# design.net
KiCad netlist of a schematic drawn in Altium Designer
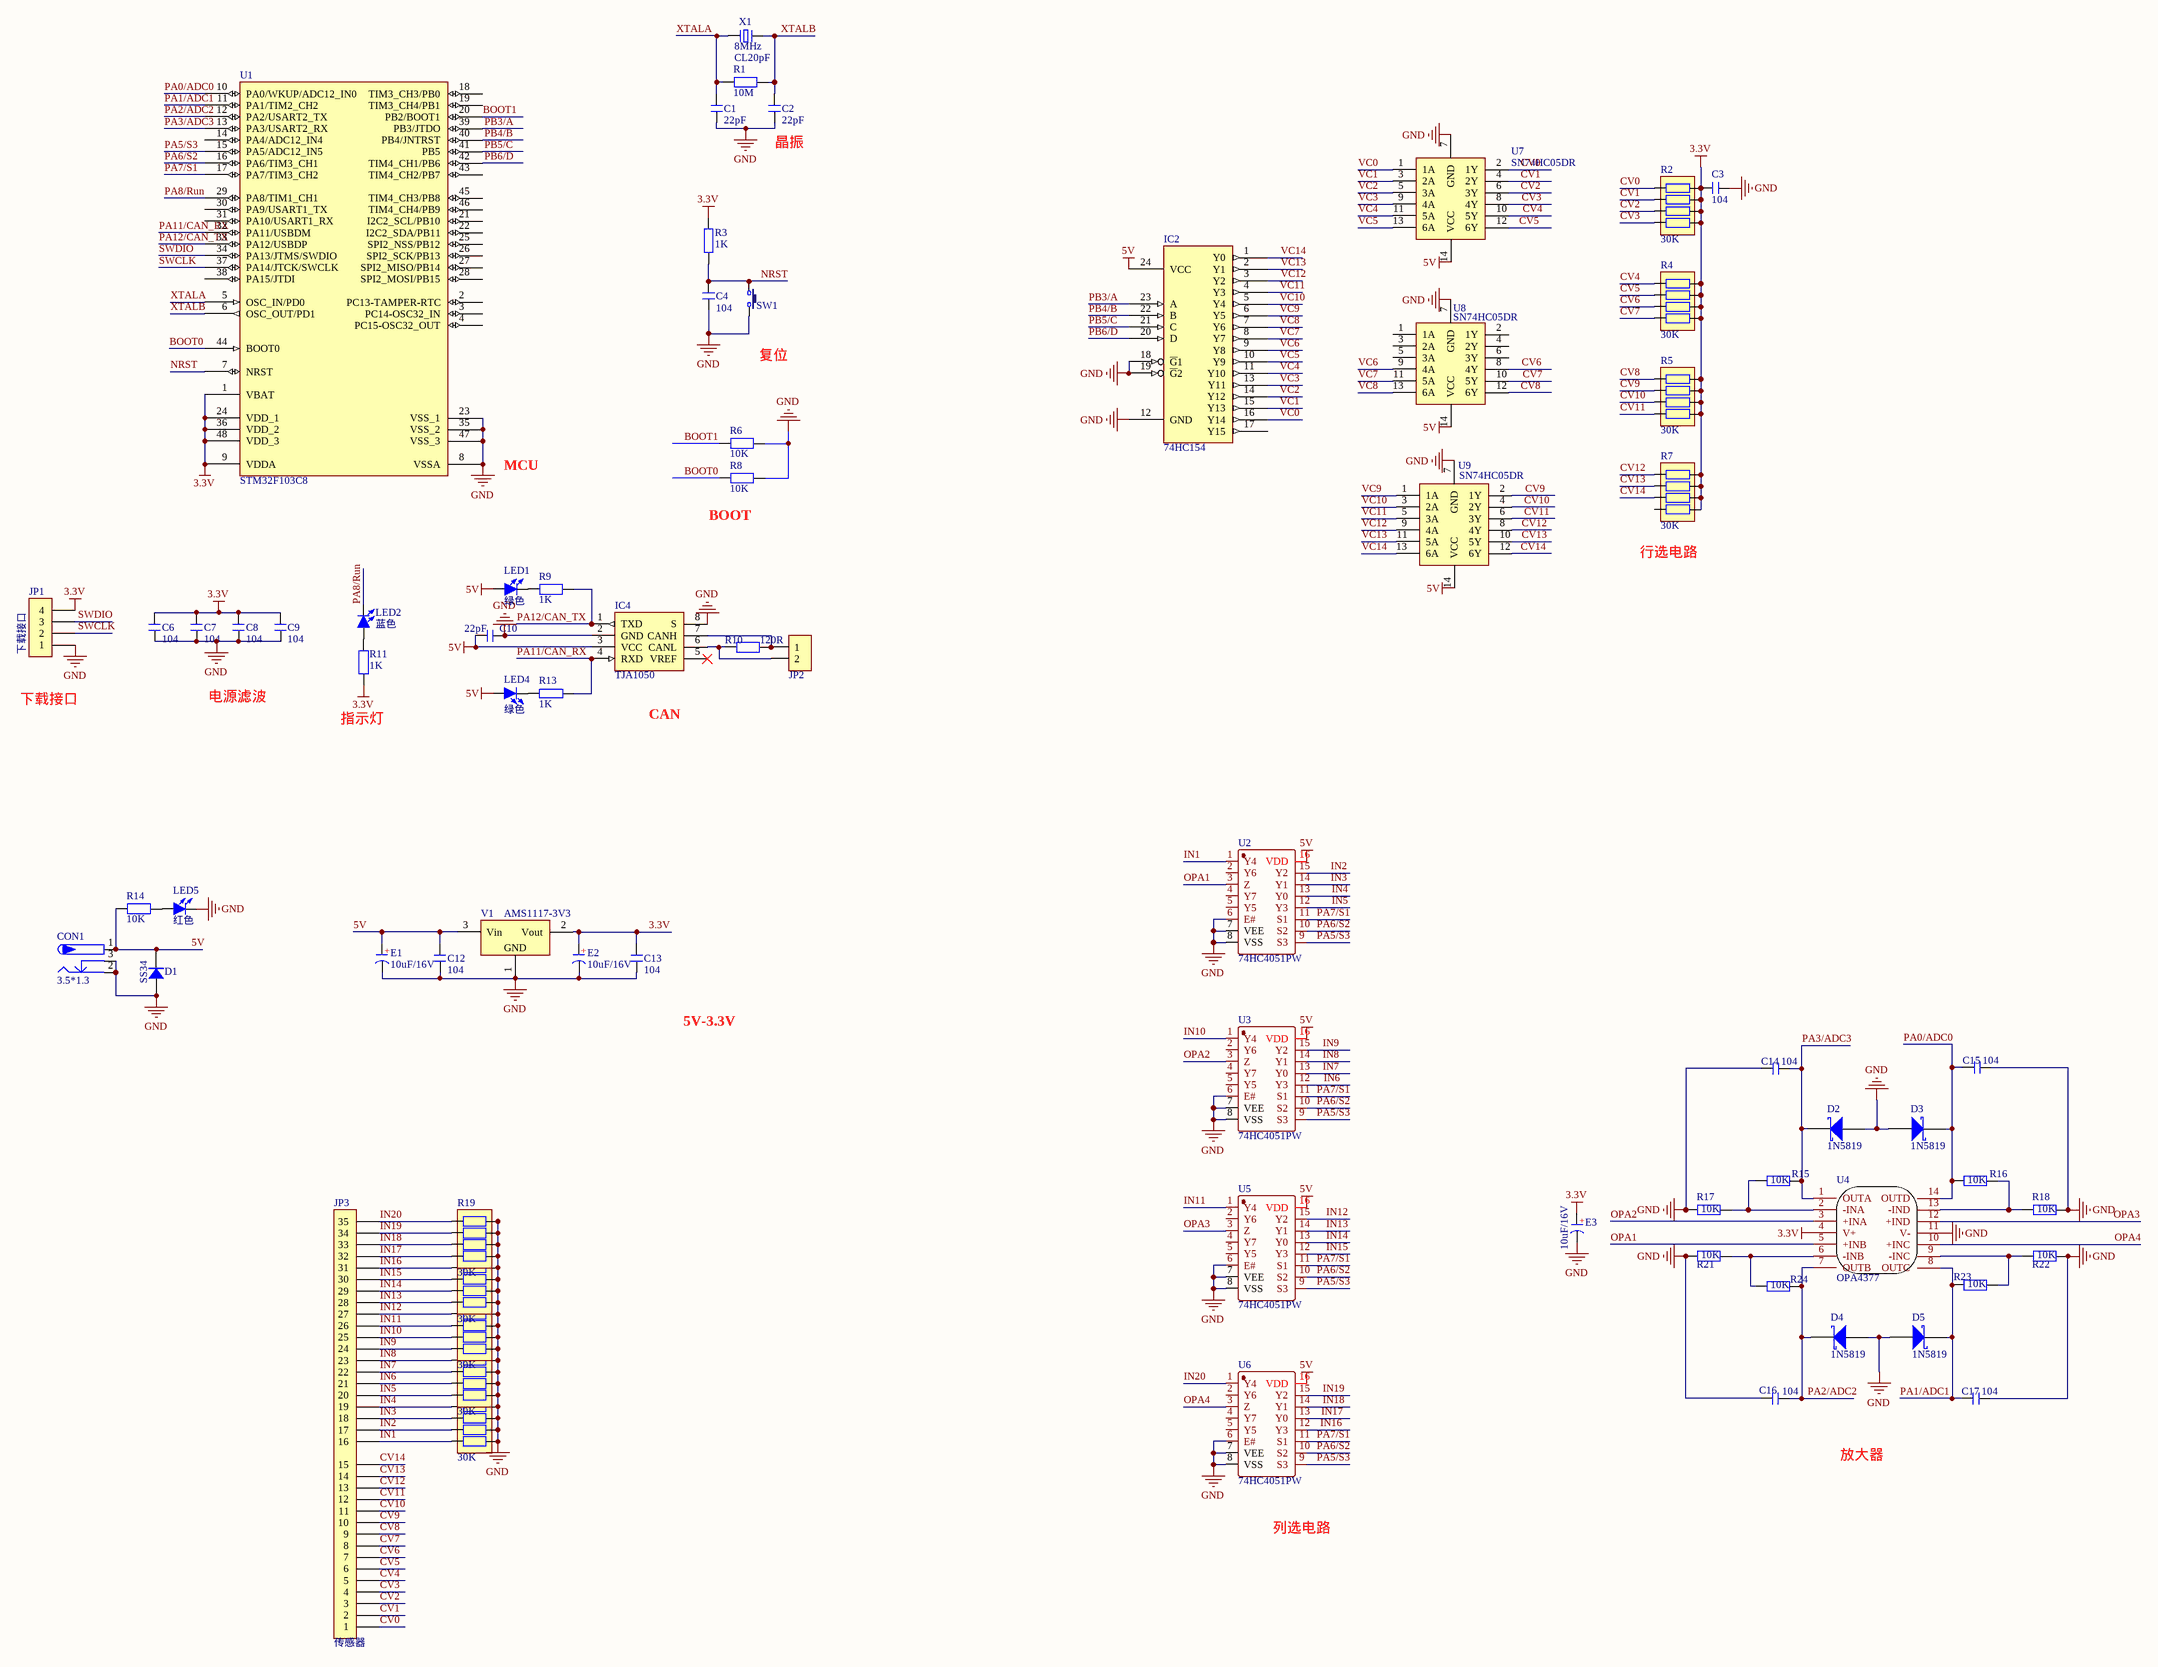
[diagram p0: 从机.SchDoc]

(export (version "E")
  (design (tool "Eeschema 10.0.6"))
  (components
    (comp (ref "C1")
      (value "22pF")
      (footprint "C 0402_L")
      (description "贴片电容")
      (libsource (lib "0.1 - 电阻-电容-电感") (part "C"))
    )
    (comp (ref "C2")
      (value "22pF")
      (footprint "C 0402_L")
      (description "贴片电容")
      (libsource (lib "0.1 - 电阻-电容-电感") (part "C"))
    )
    (comp (ref "C3")
      (value "104")
      (footprint "C 0402_L")
      (description "贴片电容")
      (libsource (lib "0.1 - 电阻-电容-电感") (part "C"))
    )
    (comp (ref "C4")
      (value "104")
      (footprint "C 0402_L")
      (description "贴片电容")
      (libsource (lib "0.1 - 电阻-电容-电感") (part "C"))
    )
    (comp (ref "C6")
      (value "104")
      (footprint "C 0402_L")
      (description "贴片电容")
      (libsource (lib "0.1 - 电阻-电容-电感") (part "C"))
    )
    (comp (ref "C7")
      (value "104")
      (footprint "C 0402_L")
      (description "贴片电容")
      (libsource (lib "0.1 - 电阻-电容-电感") (part "C"))
    )
    (comp (ref "C8")
      (value "104")
      (footprint "C 0402_L")
      (description "贴片电容")
      (libsource (lib "0.1 - 电阻-电容-电感") (part "C"))
    )
    (comp (ref "C9")
      (value "104")
      (footprint "C 0402_L")
      (description "贴片电容")
      (libsource (lib "0.1 - 电阻-电容-电感") (part "C"))
    )
    (comp (ref "C10")
      (value "22pF")
      (footprint "C 0402_L")
      (description "贴片电容")
      (libsource (lib "0.1 - 电阻-电容-电感") (part "C"))
    )
    (comp (ref "C12")
      (value "104")
      (footprint "C 0402_L")
      (description "贴片电容")
      (libsource (lib "0.1 - 电阻-电容-电感") (part "C"))
    )
    (comp (ref "C13")
      (value "104")
      (footprint "C 0402_L")
      (description "贴片电容")
      (libsource (lib "0.1 - 电阻-电容-电感") (part "C"))
    )
    (comp (ref "C14")
      (value "104")
      (footprint "C 0402_L")
      (description "贴片电容")
      (libsource (lib "0.1 - 电阻-电容-电感") (part "C"))
    )
    (comp (ref "C15")
      (value "104")
      (footprint "C 0402_L")
      (description "贴片电容")
      (libsource (lib "0.1 - 电阻-电容-电感") (part "C"))
    )
    (comp (ref "C16")
      (value "104")
      (footprint "C 0402_L")
      (description "贴片电容")
      (libsource (lib "0.1 - 电阻-电容-电感") (part "C"))
    )
    (comp (ref "C17")
      (value "104")
      (footprint "C 0402_L")
      (description "贴片电容")
      (libsource (lib "0.1 - 电阻-电容-电感") (part "C"))
    )
    (comp (ref "CON1")
      (value "3.5*1.3")
      (footprint "DC-005")
      (description "低压电源接口")
      (fields (field (name "版权归属") "源创客"))
      (libsource (lib "接口类") (part "P-DC"))
    )
    (comp (ref "D1")
      (value "SS34")
      (footprint "SMA")
      (description "肖特基二极管")
      (fields (field (name "版权归属") "源创客"))
      (libsource (lib "二极管-整流桥") (part "SS54"))
    )
    (comp (ref "D2")
      (value "1N5819")
      (footprint "SOD-123")
      (description "肖特基二极管")
      (libsource (lib "0.2 -  二极管-整流桥") (part "1N5819"))
    )
    (comp (ref "D3")
      (value "1N5819")
      (footprint "SOD-123")
      (description "肖特基二极管")
      (libsource (lib "0.2 -  二极管-整流桥") (part "1N5819"))
    )
    (comp (ref "D4")
      (value "1N5819")
      (footprint "SOD-123")
      (description "肖特基二极管")
      (libsource (lib "0.2 -  二极管-整流桥") (part "1N5819"))
    )
    (comp (ref "D5")
      (value "1N5819")
      (footprint "SOD-123")
      (description "肖特基二极管")
      (libsource (lib "0.2 -  二极管-整流桥") (part "1N5819"))
    )
    (comp (ref "E1")
      (value "10uF/16V")
      (footprint "CD A(3216)")
      (description "贴片钽电容")
      (libsource (lib "0.1 - 电阻-电容-电感") (part "CT"))
    )
    (comp (ref "E2")
      (value "10uF/16V")
      (footprint "CD A(3216)")
      (description "贴片钽电容")
      (libsource (lib "0.1 - 电阻-电容-电感") (part "CT"))
    )
    (comp (ref "E3")
      (value "10uF/16V")
      (footprint "CD A(3216)")
      (description "贴片钽电容")
      (libsource (lib "0.1 - 电阻-电容-电感") (part "CT"))
    )
    (comp (ref "IC2")
      (value "74HC154")
      (footprint "SOP24_N")
      (description "4线转16线译码器")
      (fields (field (name "版权归属") "源创客"))
      (libsource (lib "74系列芯片") (part "74HC154"))
    )
    (comp (ref "IC4")
      (value "TJA1050")
      (footprint "SOP8_L")
      (description "CAN总线收发芯片")
      (fields (field (name "版权归属") "封装库来自淘宝 ID：黄晶宝石"))
      (libsource (lib "1.0 - 常见芯片") (part "TJA1050"))
    )
    (comp (ref "JP1")
      (value "下载接口")
      (footprint "下载接口")
      (description "Jlink下载接口")
      (libsource (lib "金手指") (part "下载接口"))
    )
    (comp (ref "JP2")
      (value "HDR-1X2")
      (footprint "KF350-2P")
      (description "2P接插件")
      (fields (field (name "版权归属") "封装库来自淘宝卖家 ID：黄晶宝石"))
      (libsource (lib "5.4 - 接插件-脚距3.5") (part "Header 2"))
    )
    (comp (ref "JP3")
      (value "传感器")
      (footprint "柔性传感器")
      (description "浙清柔性阵列传感器")
      (libsource (lib "金手指") (part "传感器"))
    )
    (comp (ref "LED1")
      (value "绿色")
      (footprint "LED 0603G")
      (description "贴片LED")
      (fields (field (name "版权归属") "封装库来自淘宝 ID：黄晶宝石"))
      (libsource (lib "0.3 - LED发光二极管") (part "LED-SMD"))
    )
    (comp (ref "LED2")
      (value "蓝色")
      (footprint "LED 0603B")
      (description "贴片LED")
      (fields (field (name "版权归属") "封装库来自淘宝 ID：黄晶宝石"))
      (libsource (lib "0.3 - LED发光二极管") (part "LED-SMD"))
    )
    (comp (ref "LED4")
      (value "绿色")
      (footprint "LED 0603G")
      (description "贴片LED")
      (fields (field (name "版权归属") "封装库来自淘宝 ID：黄晶宝石"))
      (libsource (lib "0.3 - LED发光二极管") (part "LED-SMD"))
    )
    (comp (ref "LED5")
      (value "红色")
      (footprint "LED 0603R")
      (description "贴片LED")
      (fields (field (name "版权归属") "封装库来自淘宝 ID：黄晶宝石"))
      (libsource (lib "0.3 - LED发光二极管") (part "LED-SMD"))
    )
    (comp (ref "R1")
      (value "10M")
      (footprint "R 0402_L")
      (description "贴片电阻")
      (fields (field (name "版权归属") "来自淘宝 ID：黄晶宝石"))
      (libsource (lib "0.1 - 电阻-电容-电感") (part "R"))
    )
    (comp (ref "R2")
      (value "30K")
      (footprint "RCA-8P4R-0603")
      (description "贴片排阻")
      (fields (field (name "版权归属") "封装库来自淘宝 ID：黄晶宝石"))
      (libsource (lib "0.1 - 电阻-电容-电感") (part "R-8P4R"))
    )
    (comp (ref "R3")
      (value "1K")
      (footprint "R 0402_L")
      (description "贴片电阻")
      (fields (field (name "版权归属") "来自淘宝 ID：黄晶宝石"))
      (libsource (lib "0.1 - 电阻-电容-电感") (part "R"))
    )
    (comp (ref "R4")
      (value "30K")
      (footprint "RCA-8P4R-0603")
      (description "贴片排阻")
      (fields (field (name "版权归属") "封装库来自淘宝 ID：黄晶宝石"))
      (libsource (lib "0.1 - 电阻-电容-电感") (part "R-8P4R"))
    )
    (comp (ref "R5")
      (value "30K")
      (footprint "RCA-8P4R-0603")
      (description "贴片排阻")
      (fields (field (name "版权归属") "封装库来自淘宝 ID：黄晶宝石"))
      (libsource (lib "0.1 - 电阻-电容-电感") (part "R-8P4R"))
    )
    (comp (ref "R6")
      (value "10K")
      (footprint "R 0603_L")
      (description "贴片电阻")
      (fields (field (name "版权归属") "来自淘宝 ID：黄晶宝石"))
      (libsource (lib "0.1 - 电阻-电容-电感") (part "R"))
    )
    (comp (ref "R7")
      (value "30K")
      (footprint "RCA-8P4R-0603")
      (description "贴片排阻")
      (fields (field (name "版权归属") "封装库来自淘宝 ID：黄晶宝石"))
      (libsource (lib "0.1 - 电阻-电容-电感") (part "R-8P4R"))
    )
    (comp (ref "R8")
      (value "10K")
      (footprint "R 0603_L")
      (description "贴片电阻")
      (fields (field (name "版权归属") "来自淘宝 ID：黄晶宝石"))
      (libsource (lib "0.1 - 电阻-电容-电感") (part "R"))
    )
    (comp (ref "R9")
      (value "1K")
      (footprint "R 0402_L")
      (description "贴片电阻")
      (fields (field (name "版权归属") "来自淘宝 ID：黄晶宝石"))
      (libsource (lib "0.1 - 电阻-电容-电感") (part "R"))
    )
    (comp (ref "R10")
      (value "120R")
      (footprint "R 0402_L")
      (description "贴片电阻")
      (fields (field (name "版权归属") "来自淘宝 ID：黄晶宝石"))
      (libsource (lib "0.1 - 电阻-电容-电感") (part "R"))
    )
    (comp (ref "R11")
      (value "1K")
      (footprint "R 0402_L")
      (description "贴片电阻")
      (fields (field (name "版权归属") "来自淘宝 ID：黄晶宝石"))
      (libsource (lib "0.1 - 电阻-电容-电感") (part "R"))
    )
    (comp (ref "R13")
      (value "1K")
      (footprint "R 0402_L")
      (description "贴片电阻")
      (fields (field (name "版权归属") "来自淘宝 ID：黄晶宝石"))
      (libsource (lib "0.1 - 电阻-电容-电感") (part "R"))
    )
    (comp (ref "R14")
      (value "10K")
      (footprint "R 0402_L")
      (description "贴片电阻")
      (fields (field (name "版权归属") "来自淘宝 ID：黄晶宝石"))
      (libsource (lib "0.1 - 电阻-电容-电感") (part "R"))
    )
    (comp (ref "R15")
      (value "10K")
      (footprint "R 0402_L")
      (description "贴片电阻")
      (fields (field (name "版权归属") "来自淘宝 ID：黄晶宝石"))
      (libsource (lib "0.1 - 电阻-电容-电感") (part "R"))
    )
    (comp (ref "R16")
      (value "10K")
      (footprint "R 0402_L")
      (description "贴片电阻")
      (fields (field (name "版权归属") "来自淘宝 ID：黄晶宝石"))
      (libsource (lib "0.1 - 电阻-电容-电感") (part "R"))
    )
    (comp (ref "R17")
      (value "10K")
      (footprint "R 0402_L")
      (description "贴片电阻")
      (fields (field (name "版权归属") "来自淘宝 ID：黄晶宝石"))
      (libsource (lib "0.1 - 电阻-电容-电感") (part "R"))
    )
    (comp (ref "R18")
      (value "10K")
      (footprint "R 0402_L")
      (description "贴片电阻")
      (fields (field (name "版权归属") "来自淘宝 ID：黄晶宝石"))
      (libsource (lib "0.1 - 电阻-电容-电感") (part "R"))
    )
    (comp (ref "R19")
      (value "30K")
      (footprint "RCA-8P4R-0603")
      (description "贴片排阻")
      (fields (field (name "版权归属") "封装库来自淘宝 ID：黄晶宝石"))
      (libsource (lib "") (part "R-8P4R_1"))
    )
    (comp (ref "R20")
      (value "30K")
      (footprint "RCA-8P4R-0603")
      (description "贴片排阻")
      (fields (field (name "版权归属") "封装库来自淘宝 ID：黄晶宝石"))
      (libsource (lib "") (part "R-8P4R_1"))
    )
    (comp (ref "R21")
      (value "10K")
      (footprint "R 0402_L")
      (description "贴片电阻")
      (fields (field (name "版权归属") "来自淘宝 ID：黄晶宝石"))
      (libsource (lib "0.1 - 电阻-电容-电感") (part "R"))
    )
    (comp (ref "R22")
      (value "10K")
      (footprint "R 0402_L")
      (description "贴片电阻")
      (fields (field (name "版权归属") "来自淘宝 ID：黄晶宝石"))
      (libsource (lib "0.1 - 电阻-电容-电感") (part "R"))
    )
    (comp (ref "R23")
      (value "10K")
      (footprint "R 0402_L")
      (description "贴片电阻")
      (fields (field (name "版权归属") "来自淘宝 ID：黄晶宝石"))
      (libsource (lib "0.1 - 电阻-电容-电感") (part "R"))
    )
    (comp (ref "R24")
      (value "10K")
      (footprint "R 0402_L")
      (description "贴片电阻")
      (fields (field (name "版权归属") "来自淘宝 ID：黄晶宝石"))
      (libsource (lib "0.1 - 电阻-电容-电感") (part "R"))
    )
    (comp (ref "R25")
      (value "30K")
      (footprint "RCA-8P4R-0603")
      (description "贴片排阻")
      (fields (field (name "版权归属") "封装库来自淘宝 ID：黄晶宝石"))
      (libsource (lib "") (part "R-8P4R_1"))
    )
    (comp (ref "R26")
      (value "30K")
      (footprint "RCA-8P4R-0603")
      (description "贴片排阻")
      (fields (field (name "版权归属") "封装库来自淘宝 ID：黄晶宝石"))
      (libsource (lib "") (part "R-8P4R_1"))
    )
    (comp (ref "R27")
      (value "30K")
      (footprint "RCA-8P4R-0603")
      (description "贴片排阻")
      (fields (field (name "版权归属") "封装库来自淘宝 ID：黄晶宝石"))
      (libsource (lib "") (part "R-8P4R_1"))
    )
    (comp (ref "SW1")
      (value "3x6x5")
      (footprint "TSW SMD-3*6*2.5")
      (description "3x6轻触开关")
      (fields (field (name "版权归属") "源创客"))
      (libsource (lib "按键-开关") (part "TSW 3x6"))
    )
    (comp (ref "U1")
      (value "STM32F103C8")
      (footprint "LQFP48 7X7_L")
      (description "Flaah:64/RAM:20/IO:36")
      (fields (field (name "版权归属") "源创客"))
      (libsource (lib "STM32系列单片机") (part "STM32F103C8"))
    )
    (comp (ref "U2")
      (value "74HC4051PW")
      (footprint "TSSOP16_N")
      (libsource (lib "1.4 - 74系列TTL芯片") (part "74HC4051PW"))
    )
    (comp (ref "U3")
      (value "74HC4051PW")
      (footprint "TSSOP16_N")
      (libsource (lib "1.4 - 74系列TTL芯片") (part "74HC4051PW"))
    )
    (comp (ref "U4")
      (value "OPA4377")
      (footprint "TSSOP14_L")
      (description "4路运放")
      (libsource (lib "运放-功放") (part "OPA4377"))
    )
    (comp (ref "U5")
      (value "74HC4051PW")
      (footprint "TSSOP16_N")
      (libsource (lib "1.4 - 74系列TTL芯片") (part "74HC4051PW"))
    )
    (comp (ref "U6")
      (value "74HC4051PW")
      (footprint "TSSOP16_N")
      (libsource (lib "1.4 - 74系列TTL芯片") (part "74HC4051PW"))
    )
    (comp (ref "U7")
      (value "SN74HC05DR")
      (footprint "SOP14")
      (libsource (lib "1.4 - 74系列TTL芯片") (part "SN74HC05DR"))
    )
    (comp (ref "U8")
      (value "SN74HC05DR")
      (footprint "SOP14")
      (libsource (lib "1.4 - 74系列TTL芯片") (part "SN74HC05DR"))
    )
    (comp (ref "U9")
      (value "SN74HC05DR")
      (footprint "SOP14")
      (libsource (lib "1.4 - 74系列TTL芯片") (part "SN74HC05DR"))
    )
    (comp (ref "V1")
      (value "AMS1117-3V3")
      (footprint "SOT223_L")
      (description "三端稳压芯片")
      (libsource (lib "1.1 - 电源类芯片") (part "AMS1117"))
    )
    (comp (ref "X1")
      (value "8MHz")
      (footprint "OSC 5032-2P")
      (description "2脚无源脚晶振")
      (fields (field (name "负载电容") "CL20pF") (field (name "版权归属") "源创客"))
      (libsource (lib "保险丝-晶振") (part "XTAL-2P"))
    )
  )
  (nets
    (net (code "1") (name "/BOOT0") (class "Default")
      (node (ref "R8") (pin "1") (pinfunction "1_1") (pintype "passive"))
      (node (ref "U1") (pin "44") (pinfunction "BOOT0_44") (pintype "input"))
    )
    (net (code "2") (name "/BOOT1") (class "Default")
      (node (ref "R6") (pin "1") (pinfunction "1_1") (pintype "passive"))
      (node (ref "U1") (pin "20") (pinfunction "PB2/BOOT1_20") (pintype "bidirectional"))
    )
    (net (code "3") (name "/CV0") (class "Default")
      (node (ref "JP3") (pin "1") (pinfunction "1_1") (pintype "passive"))
      (node (ref "R2") (pin "8") (pinfunction "8_8") (pintype "passive"))
      (node (ref "U7") (pin "2") (pinfunction "1Y_2") (pintype "passive"))
    )
    (net (code "4") (name "/CV1") (class "Default")
      (node (ref "JP3") (pin "2") (pinfunction "2_2") (pintype "passive"))
      (node (ref "R2") (pin "7") (pinfunction "7_7") (pintype "passive"))
      (node (ref "U7") (pin "4") (pinfunction "2Y_4") (pintype "passive"))
    )
    (net (code "5") (name "/CV2") (class "Default")
      (node (ref "JP3") (pin "3") (pinfunction "3_3") (pintype "passive"))
      (node (ref "R2") (pin "6") (pinfunction "6_6") (pintype "passive"))
      (node (ref "U7") (pin "6") (pinfunction "3Y_6") (pintype "passive"))
    )
    (net (code "6") (name "/CV3") (class "Default")
      (node (ref "JP3") (pin "4") (pinfunction "4_4") (pintype "passive"))
      (node (ref "R2") (pin "5") (pinfunction "5_5") (pintype "passive"))
      (node (ref "U7") (pin "8") (pinfunction "4Y_8") (pintype "passive"))
    )
    (net (code "7") (name "/CV4") (class "Default")
      (node (ref "JP3") (pin "5") (pinfunction "5_5") (pintype "passive"))
      (node (ref "R4") (pin "8") (pinfunction "8_8") (pintype "passive"))
      (node (ref "U7") (pin "10") (pinfunction "5Y_10") (pintype "passive"))
    )
    (net (code "8") (name "/CV5") (class "Default")
      (node (ref "JP3") (pin "6") (pinfunction "6_6") (pintype "passive"))
      (node (ref "R4") (pin "7") (pinfunction "7_7") (pintype "passive"))
      (node (ref "U7") (pin "12") (pinfunction "6Y_12") (pintype "passive"))
    )
    (net (code "9") (name "/CV6") (class "Default")
      (node (ref "JP3") (pin "7") (pinfunction "7_7") (pintype "passive"))
      (node (ref "R4") (pin "6") (pinfunction "6_6") (pintype "passive"))
      (node (ref "U8") (pin "8") (pinfunction "4Y_8") (pintype "passive"))
    )
    (net (code "10") (name "/CV7") (class "Default")
      (node (ref "JP3") (pin "8") (pinfunction "8_8") (pintype "passive"))
      (node (ref "R4") (pin "5") (pinfunction "5_5") (pintype "passive"))
      (node (ref "U8") (pin "10") (pinfunction "5Y_10") (pintype "passive"))
    )
    (net (code "11") (name "/CV8") (class "Default")
      (node (ref "JP3") (pin "9") (pinfunction "9_9") (pintype "passive"))
      (node (ref "R5") (pin "8") (pinfunction "8_8") (pintype "passive"))
      (node (ref "U8") (pin "12") (pinfunction "6Y_12") (pintype "passive"))
    )
    (net (code "12") (name "/CV9") (class "Default")
      (node (ref "JP3") (pin "10") (pinfunction "10_10") (pintype "passive"))
      (node (ref "R5") (pin "7") (pinfunction "7_7") (pintype "passive"))
      (node (ref "U9") (pin "2") (pinfunction "1Y_2") (pintype "passive"))
    )
    (net (code "13") (name "/CV10") (class "Default")
      (node (ref "JP3") (pin "11") (pinfunction "11_11") (pintype "passive"))
      (node (ref "R5") (pin "6") (pinfunction "6_6") (pintype "passive"))
      (node (ref "U9") (pin "4") (pinfunction "2Y_4") (pintype "passive"))
    )
    (net (code "14") (name "/CV11") (class "Default")
      (node (ref "JP3") (pin "12") (pinfunction "12_12") (pintype "passive"))
      (node (ref "R5") (pin "5") (pinfunction "5_5") (pintype "passive"))
      (node (ref "U9") (pin "6") (pinfunction "3Y_6") (pintype "passive"))
    )
    (net (code "15") (name "/CV12") (class "Default")
      (node (ref "JP3") (pin "13") (pinfunction "13_13") (pintype "passive"))
      (node (ref "R7") (pin "8") (pinfunction "8_8") (pintype "passive"))
      (node (ref "U9") (pin "8") (pinfunction "4Y_8") (pintype "passive"))
    )
    (net (code "16") (name "/CV13") (class "Default")
      (node (ref "JP3") (pin "14") (pinfunction "14_14") (pintype "passive"))
      (node (ref "R7") (pin "7") (pinfunction "7_7") (pintype "passive"))
      (node (ref "U9") (pin "10") (pinfunction "5Y_10") (pintype "passive"))
    )
    (net (code "17") (name "/CV14") (class "Default")
      (node (ref "JP3") (pin "15") (pinfunction "15_15") (pintype "passive"))
      (node (ref "R7") (pin "6") (pinfunction "6_6") (pintype "passive"))
      (node (ref "U9") (pin "12") (pinfunction "6Y_12") (pintype "passive"))
    )
    (net (code "18") (name "/IN1") (class "Default")
      (node (ref "JP3") (pin "16") (pinfunction "16_16") (pintype "passive"))
      (node (ref "R27") (pin "8") (pinfunction "8_8") (pintype "passive"))
      (node (ref "U2") (pin "1") (pinfunction "Y4_1") (pintype "passive"))
    )
    (net (code "19") (name "/IN2") (class "Default")
      (node (ref "JP3") (pin "17") (pinfunction "17_17") (pintype "passive"))
      (node (ref "R27") (pin "7") (pinfunction "7_7") (pintype "passive"))
      (node (ref "U2") (pin "15") (pinfunction "Y2_15") (pintype "passive"))
    )
    (net (code "20") (name "/IN3") (class "Default")
      (node (ref "JP3") (pin "18") (pinfunction "18_18") (pintype "passive"))
      (node (ref "R27") (pin "6") (pinfunction "6_6") (pintype "passive"))
      (node (ref "U2") (pin "14") (pinfunction "Y1_14") (pintype "passive"))
    )
    (net (code "21") (name "/IN4") (class "Default")
      (node (ref "JP3") (pin "19") (pinfunction "19_19") (pintype "passive"))
      (node (ref "R27") (pin "5") (pinfunction "5_5") (pintype "passive"))
      (node (ref "U2") (pin "13") (pinfunction "Y0_13") (pintype "passive"))
    )
    (net (code "22") (name "/IN5") (class "Default")
      (node (ref "JP3") (pin "20") (pinfunction "20_20") (pintype "passive"))
      (node (ref "R26") (pin "8") (pinfunction "8_8") (pintype "passive"))
      (node (ref "U2") (pin "12") (pinfunction "Y3_12") (pintype "passive"))
    )
    (net (code "23") (name "/IN6") (class "Default")
      (node (ref "JP3") (pin "21") (pinfunction "21_21") (pintype "passive"))
      (node (ref "R26") (pin "7") (pinfunction "7_7") (pintype "passive"))
      (node (ref "U3") (pin "12") (pinfunction "Y3_12") (pintype "passive"))
    )
    (net (code "24") (name "/IN7") (class "Default")
      (node (ref "JP3") (pin "22") (pinfunction "22_22") (pintype "passive"))
      (node (ref "R26") (pin "6") (pinfunction "6_6") (pintype "passive"))
      (node (ref "U3") (pin "13") (pinfunction "Y0_13") (pintype "passive"))
    )
    (net (code "25") (name "/IN8") (class "Default")
      (node (ref "JP3") (pin "23") (pinfunction "23_23") (pintype "passive"))
      (node (ref "R26") (pin "5") (pinfunction "5_5") (pintype "passive"))
      (node (ref "U3") (pin "14") (pinfunction "Y1_14") (pintype "passive"))
    )
    (net (code "26") (name "/IN9") (class "Default")
      (node (ref "JP3") (pin "24") (pinfunction "24_24") (pintype "passive"))
      (node (ref "R25") (pin "8") (pinfunction "8_8") (pintype "passive"))
      (node (ref "U3") (pin "15") (pinfunction "Y2_15") (pintype "passive"))
    )
    (net (code "27") (name "/IN10") (class "Default")
      (node (ref "JP3") (pin "25") (pinfunction "25_25") (pintype "passive"))
      (node (ref "R25") (pin "7") (pinfunction "7_7") (pintype "passive"))
      (node (ref "U3") (pin "1") (pinfunction "Y4_1") (pintype "passive"))
    )
    (net (code "28") (name "/IN11") (class "Default")
      (node (ref "JP3") (pin "26") (pinfunction "26_26") (pintype "passive"))
      (node (ref "R25") (pin "6") (pinfunction "6_6") (pintype "passive"))
      (node (ref "U5") (pin "1") (pinfunction "Y4_1") (pintype "passive"))
    )
    (net (code "29") (name "/IN12") (class "Default")
      (node (ref "JP3") (pin "27") (pinfunction "27_27") (pintype "passive"))
      (node (ref "R25") (pin "5") (pinfunction "5_5") (pintype "passive"))
      (node (ref "U5") (pin "15") (pinfunction "Y2_15") (pintype "passive"))
    )
    (net (code "30") (name "/IN13") (class "Default")
      (node (ref "JP3") (pin "28") (pinfunction "28_28") (pintype "passive"))
      (node (ref "R20") (pin "8") (pinfunction "8_8") (pintype "passive"))
      (node (ref "U5") (pin "14") (pinfunction "Y1_14") (pintype "passive"))
    )
    (net (code "31") (name "/IN14") (class "Default")
      (node (ref "JP3") (pin "29") (pinfunction "29_29") (pintype "passive"))
      (node (ref "R20") (pin "7") (pinfunction "7_7") (pintype "passive"))
      (node (ref "U5") (pin "13") (pinfunction "Y0_13") (pintype "passive"))
    )
    (net (code "32") (name "/IN15") (class "Default")
      (node (ref "JP3") (pin "30") (pinfunction "30_30") (pintype "passive"))
      (node (ref "R20") (pin "6") (pinfunction "6_6") (pintype "passive"))
      (node (ref "U5") (pin "12") (pinfunction "Y3_12") (pintype "passive"))
    )
    (net (code "33") (name "/IN16") (class "Default")
      (node (ref "JP3") (pin "31") (pinfunction "31_31") (pintype "passive"))
      (node (ref "R20") (pin "5") (pinfunction "5_5") (pintype "passive"))
      (node (ref "U6") (pin "12") (pinfunction "Y3_12") (pintype "passive"))
    )
    (net (code "34") (name "/IN17") (class "Default")
      (node (ref "JP3") (pin "32") (pinfunction "32_32") (pintype "passive"))
      (node (ref "R19") (pin "8") (pinfunction "8_8") (pintype "passive"))
      (node (ref "U6") (pin "13") (pinfunction "Y0_13") (pintype "passive"))
    )
    (net (code "35") (name "/IN18") (class "Default")
      (node (ref "JP3") (pin "33") (pinfunction "33_33") (pintype "passive"))
      (node (ref "R19") (pin "7") (pinfunction "7_7") (pintype "passive"))
      (node (ref "U6") (pin "14") (pinfunction "Y1_14") (pintype "passive"))
    )
    (net (code "36") (name "/IN19") (class "Default")
      (node (ref "JP3") (pin "34") (pinfunction "34_34") (pintype "passive"))
      (node (ref "R19") (pin "6") (pinfunction "6_6") (pintype "passive"))
      (node (ref "U6") (pin "15") (pinfunction "Y2_15") (pintype "passive"))
    )
    (net (code "37") (name "/IN20") (class "Default")
      (node (ref "JP3") (pin "35") (pinfunction "35_35") (pintype "passive"))
      (node (ref "R19") (pin "5") (pinfunction "5_5") (pintype "passive"))
      (node (ref "U6") (pin "1") (pinfunction "Y4_1") (pintype "passive"))
    )
    (net (code "38") (name "/NRST") (class "Default")
      (node (ref "C4") (pin "2") (pinfunction "2_2") (pintype "passive"))
      (node (ref "R3") (pin "1") (pinfunction "1_1") (pintype "passive"))
      (node (ref "SW1") (pin "1") (pinfunction "1_1") (pintype "passive"))
      (node (ref "U1") (pin "7") (pinfunction "NRST_7") (pintype "bidirectional"))
    )
    (net (code "39") (name "/OPA1") (class "Default")
      (node (ref "U2") (pin "3") (pinfunction "Z_3") (pintype "passive"))
      (node (ref "U4") (pin "5") (pinfunction "+INB_5") (pintype "passive"))
    )
    (net (code "40") (name "/OPA2") (class "Default")
      (node (ref "U3") (pin "3") (pinfunction "Z_3") (pintype "passive"))
      (node (ref "U4") (pin "3") (pinfunction "+INA_3") (pintype "passive"))
    )
    (net (code "41") (name "/OPA3") (class "Default")
      (node (ref "U4") (pin "12") (pinfunction "+IND_12") (pintype "passive"))
      (node (ref "U5") (pin "3") (pinfunction "Z_3") (pintype "passive"))
    )
    (net (code "42") (name "/OPA4") (class "Default")
      (node (ref "U4") (pin "10") (pinfunction "+INC_10") (pintype "passive"))
      (node (ref "U6") (pin "3") (pinfunction "Z_3") (pintype "passive"))
    )
    (net (code "43") (name "/PA0{slash}ADC0") (class "Default")
      (node (ref "C15") (pin "1") (pinfunction "1_1") (pintype "passive"))
      (node (ref "D3") (pin "2") (pinfunction "K_2") (pintype "passive"))
      (node (ref "R16") (pin "1") (pinfunction "1_1") (pintype "passive"))
      (node (ref "U1") (pin "10") (pinfunction "PA0/WKUP/ADC12_IN0_10") (pintype "bidirectional"))
      (node (ref "U4") (pin "14") (pinfunction "OUTD_14") (pintype "passive"))
    )
    (net (code "44") (name "/PA1{slash}ADC1") (class "Default")
      (node (ref "C17") (pin "1") (pinfunction "1_1") (pintype "passive"))
      (node (ref "D5") (pin "2") (pinfunction "K_2") (pintype "passive"))
      (node (ref "R23") (pin "1") (pinfunction "1_1") (pintype "passive"))
      (node (ref "U1") (pin "11") (pinfunction "PA1/TIM2_CH2_11") (pintype "bidirectional"))
      (node (ref "U4") (pin "8") (pinfunction "OUTC_8") (pintype "passive"))
    )
    (net (code "45") (name "/PA2{slash}ADC2") (class "Default")
      (node (ref "C16") (pin "1") (pinfunction "1_1") (pintype "passive"))
      (node (ref "D4") (pin "2") (pinfunction "K_2") (pintype "passive"))
      (node (ref "R24") (pin "2") (pinfunction "2_2") (pintype "passive"))
      (node (ref "U1") (pin "12") (pinfunction "PA2/USART2_TX_12") (pintype "bidirectional"))
      (node (ref "U4") (pin "7") (pinfunction "OUTB_7") (pintype "passive"))
    )
    (net (code "46") (name "/PA3{slash}ADC3") (class "Default")
      (node (ref "C14") (pin "2") (pinfunction "2_2") (pintype "passive"))
      (node (ref "D2") (pin "2") (pinfunction "K_2") (pintype "passive"))
      (node (ref "R15") (pin "2") (pinfunction "2_2") (pintype "passive"))
      (node (ref "U1") (pin "13") (pinfunction "PA3/USART2_RX_13") (pintype "bidirectional"))
      (node (ref "U4") (pin "1") (pinfunction "OUTA_1") (pintype "passive"))
    )
    (net (code "47") (name "/PA5{slash}S3") (class "Default")
      (node (ref "U1") (pin "15") (pinfunction "PA5/ADC12_IN5_15") (pintype "bidirectional"))
      (node (ref "U2") (pin "9") (pinfunction "S3_9") (pintype "passive"))
      (node (ref "U3") (pin "9") (pinfunction "S3_9") (pintype "passive"))
      (node (ref "U5") (pin "9") (pinfunction "S3_9") (pintype "passive"))
      (node (ref "U6") (pin "9") (pinfunction "S3_9") (pintype "passive"))
    )
    (net (code "48") (name "/PA6{slash}S2") (class "Default")
      (node (ref "U1") (pin "16") (pinfunction "PA6/TIM3_CH1_16") (pintype "bidirectional"))
      (node (ref "U2") (pin "10") (pinfunction "S2_10") (pintype "passive"))
      (node (ref "U3") (pin "10") (pinfunction "S2_10") (pintype "passive"))
      (node (ref "U5") (pin "10") (pinfunction "S2_10") (pintype "passive"))
      (node (ref "U6") (pin "10") (pinfunction "S2_10") (pintype "passive"))
    )
    (net (code "49") (name "/PA7{slash}S1") (class "Default")
      (node (ref "U1") (pin "17") (pinfunction "PA7/TIM3_CH2_17") (pintype "bidirectional"))
      (node (ref "U2") (pin "11") (pinfunction "S1_11") (pintype "passive"))
      (node (ref "U3") (pin "11") (pinfunction "S1_11") (pintype "passive"))
      (node (ref "U5") (pin "11") (pinfunction "S1_11") (pintype "passive"))
      (node (ref "U6") (pin "11") (pinfunction "S1_11") (pintype "passive"))
    )
    (net (code "50") (name "/PA8{slash}Run") (class "Default")
      (node (ref "LED2") (pin "2") (pinfunction "K_2") (pintype "passive"))
      (node (ref "U1") (pin "29") (pinfunction "PA8/TIM1_CH1_29") (pintype "bidirectional"))
    )
    (net (code "51") (name "/PA11{slash}CAN_RX") (class "Default")
      (node (ref "IC4") (pin "4") (pinfunction "RXD_4") (pintype "input"))
      (node (ref "R13") (pin "1") (pinfunction "1_1") (pintype "passive"))
      (node (ref "U1") (pin "32") (pinfunction "PA11/USBDM_32") (pintype "bidirectional"))
    )
    (net (code "52") (name "/PA12{slash}CAN_TX") (class "Default")
      (node (ref "IC4") (pin "1") (pinfunction "TXD_1") (pintype "output"))
      (node (ref "R9") (pin "1") (pinfunction "1_1") (pintype "passive"))
      (node (ref "U1") (pin "33") (pinfunction "PA12/USBDP_33") (pintype "bidirectional"))
    )
    (net (code "53") (name "/PB3{slash}A") (class "Default")
      (node (ref "IC2") (pin "23") (pinfunction "A_23") (pintype "input"))
      (node (ref "U1") (pin "39") (pinfunction "PB3/JTDO_39") (pintype "bidirectional"))
    )
    (net (code "54") (name "/PB4{slash}B") (class "Default")
      (node (ref "IC2") (pin "22") (pinfunction "B_22") (pintype "input"))
      (node (ref "U1") (pin "40") (pinfunction "PB4/JNTRST_40") (pintype "bidirectional"))
    )
    (net (code "55") (name "/PB5{slash}C") (class "Default")
      (node (ref "IC2") (pin "21") (pinfunction "C_21") (pintype "input"))
      (node (ref "U1") (pin "41") (pinfunction "PB5_41") (pintype "bidirectional"))
    )
    (net (code "56") (name "/PB6{slash}D") (class "Default")
      (node (ref "IC2") (pin "20") (pinfunction "D_20") (pintype "input"))
      (node (ref "U1") (pin "42") (pinfunction "TIM4_CH1/PB6_42") (pintype "bidirectional"))
    )
    (net (code "57") (name "/SWCLK") (class "Default")
      (node (ref "JP1") (pin "2") (pinfunction "2_2") (pintype "passive"))
      (node (ref "U1") (pin "37") (pinfunction "PA14/JTCK/SWCLK_37") (pintype "bidirectional"))
    )
    (net (code "58") (name "/SWDIO") (class "Default")
      (node (ref "JP1") (pin "3") (pinfunction "3_3") (pintype "passive"))
      (node (ref "U1") (pin "34") (pinfunction "PA13/JTMS/SWDIO_34") (pintype "bidirectional"))
    )
    (net (code "59") (name "/VC0") (class "Default")
      (node (ref "IC2") (pin "16") (pinfunction "Y14_16") (pintype "output"))
      (node (ref "U7") (pin "1") (pinfunction "1A_1") (pintype "passive"))
    )
    (net (code "60") (name "/VC1") (class "Default")
      (node (ref "IC2") (pin "15") (pinfunction "Y13_15") (pintype "output"))
      (node (ref "U7") (pin "3") (pinfunction "2A_3") (pintype "passive"))
    )
    (net (code "61") (name "/VC2") (class "Default")
      (node (ref "IC2") (pin "14") (pinfunction "Y12_14") (pintype "output"))
      (node (ref "U7") (pin "5") (pinfunction "3A_5") (pintype "passive"))
    )
    (net (code "62") (name "/VC3") (class "Default")
      (node (ref "IC2") (pin "13") (pinfunction "Y11_13") (pintype "output"))
      (node (ref "U7") (pin "9") (pinfunction "4A_9") (pintype "passive"))
    )
    (net (code "63") (name "/VC4") (class "Default")
      (node (ref "IC2") (pin "11") (pinfunction "Y10_11") (pintype "output"))
      (node (ref "U7") (pin "11") (pinfunction "5A_11") (pintype "passive"))
    )
    (net (code "64") (name "/VC5") (class "Default")
      (node (ref "IC2") (pin "10") (pinfunction "Y9_10") (pintype "output"))
      (node (ref "U7") (pin "13") (pinfunction "6A_13") (pintype "passive"))
    )
    (net (code "65") (name "/VC6") (class "Default")
      (node (ref "IC2") (pin "9") (pinfunction "Y8_9") (pintype "output"))
      (node (ref "U8") (pin "9") (pinfunction "4A_9") (pintype "passive"))
    )
    (net (code "66") (name "/VC7") (class "Default")
      (node (ref "IC2") (pin "8") (pinfunction "Y7_8") (pintype "output"))
      (node (ref "U8") (pin "11") (pinfunction "5A_11") (pintype "passive"))
    )
    (net (code "67") (name "/VC8") (class "Default")
      (node (ref "IC2") (pin "7") (pinfunction "Y6_7") (pintype "output"))
      (node (ref "U8") (pin "13") (pinfunction "6A_13") (pintype "passive"))
    )
    (net (code "68") (name "/VC9") (class "Default")
      (node (ref "IC2") (pin "6") (pinfunction "Y5_6") (pintype "output"))
      (node (ref "U9") (pin "1") (pinfunction "1A_1") (pintype "passive"))
    )
    (net (code "69") (name "/VC10") (class "Default")
      (node (ref "IC2") (pin "5") (pinfunction "Y4_5") (pintype "output"))
      (node (ref "U9") (pin "3") (pinfunction "2A_3") (pintype "passive"))
    )
    (net (code "70") (name "/VC11") (class "Default")
      (node (ref "IC2") (pin "4") (pinfunction "Y3_4") (pintype "output"))
      (node (ref "U9") (pin "5") (pinfunction "3A_5") (pintype "passive"))
    )
    (net (code "71") (name "/VC12") (class "Default")
      (node (ref "IC2") (pin "3") (pinfunction "Y2_3") (pintype "output"))
      (node (ref "U9") (pin "9") (pinfunction "4A_9") (pintype "passive"))
    )
    (net (code "72") (name "/VC13") (class "Default")
      (node (ref "IC2") (pin "2") (pinfunction "Y1_2") (pintype "output"))
      (node (ref "U9") (pin "11") (pinfunction "5A_11") (pintype "passive"))
    )
    (net (code "73") (name "/VC14") (class "Default")
      (node (ref "IC2") (pin "1") (pinfunction "Y0_1") (pintype "output"))
      (node (ref "U9") (pin "13") (pinfunction "6A_13") (pintype "passive"))
    )
    (net (code "74") (name "/XTALA") (class "Default")
      (node (ref "C1") (pin "2") (pinfunction "2_2") (pintype "passive"))
      (node (ref "R1") (pin "1") (pinfunction "1_1") (pintype "passive"))
      (node (ref "U1") (pin "5") (pinfunction "OSC_IN/PD0_5") (pintype "input"))
      (node (ref "X1") (pin "1") (pinfunction "1_1") (pintype "passive"))
    )
    (net (code "75") (name "/XTALB") (class "Default")
      (node (ref "C2") (pin "2") (pinfunction "2_2") (pintype "passive"))
      (node (ref "R1") (pin "2") (pinfunction "2_2") (pintype "passive"))
      (node (ref "U1") (pin "6") (pinfunction "OSC_OUT/PD1_6") (pintype "output"))
      (node (ref "X1") (pin "2") (pinfunction "2_2") (pintype "passive"))
    )
    (net (code "76") (name "3.3V") (class "Default")
      (node (ref "C13") (pin "2") (pinfunction "2_2") (pintype "passive"))
      (node (ref "C3") (pin "1") (pinfunction "1_1") (pintype "passive"))
      (node (ref "C6") (pin "2") (pinfunction "2_2") (pintype "passive"))
      (node (ref "C7") (pin "2") (pinfunction "2_2") (pintype "passive"))
      (node (ref "C8") (pin "2") (pinfunction "2_2") (pintype "passive"))
      (node (ref "C9") (pin "2") (pinfunction "2_2") (pintype "passive"))
      (node (ref "E2") (pin "1") (pinfunction "A_1") (pintype "passive"))
      (node (ref "E3") (pin "1") (pinfunction "A_1") (pintype "passive"))
      (node (ref "JP1") (pin "4") (pinfunction "4_4") (pintype "passive"))
      (node (ref "R11") (pin "2") (pinfunction "2_2") (pintype "passive"))
      (node (ref "R2") (pin "1") (pinfunction "1_1") (pintype "passive"))
      (node (ref "R2") (pin "2") (pinfunction "2_2") (pintype "passive"))
      (node (ref "R2") (pin "3") (pinfunction "3_3") (pintype "passive"))
      (node (ref "R2") (pin "4") (pinfunction "4_4") (pintype "passive"))
      (node (ref "R3") (pin "2") (pinfunction "2_2") (pintype "passive"))
      (node (ref "R4") (pin "1") (pinfunction "1_1") (pintype "passive"))
      (node (ref "R4") (pin "2") (pinfunction "2_2") (pintype "passive"))
      (node (ref "R4") (pin "3") (pinfunction "3_3") (pintype "passive"))
      (node (ref "R4") (pin "4") (pinfunction "4_4") (pintype "passive"))
      (node (ref "R5") (pin "1") (pinfunction "1_1") (pintype "passive"))
      (node (ref "R5") (pin "2") (pinfunction "2_2") (pintype "passive"))
      (node (ref "R5") (pin "3") (pinfunction "3_3") (pintype "passive"))
      (node (ref "R5") (pin "4") (pinfunction "4_4") (pintype "passive"))
      (node (ref "R7") (pin "1") (pinfunction "1_1") (pintype "passive"))
      (node (ref "R7") (pin "2") (pinfunction "2_2") (pintype "passive"))
      (node (ref "R7") (pin "3") (pinfunction "3_3") (pintype "passive"))
      (node (ref "R7") (pin "4") (pinfunction "4_4") (pintype "passive"))
      (node (ref "U1") (pin "1") (pinfunction "VBAT_1") (pintype "power_in"))
      (node (ref "U1") (pin "24") (pinfunction "VDD_1_24") (pintype "power_in"))
      (node (ref "U1") (pin "36") (pinfunction "VDD_2_36") (pintype "power_in"))
      (node (ref "U1") (pin "48") (pinfunction "VDD_3_48") (pintype "power_in"))
      (node (ref "U1") (pin "9") (pinfunction "VDDA_9") (pintype "power_in"))
      (node (ref "U4") (pin "4") (pinfunction "V+_4") (pintype "passive"))
      (node (ref "V1") (pin "2") (pinfunction "Vout_2") (pintype "passive"))
    )
    (net (code "77") (name "5V") (class "Default")
      (node (ref "C10") (pin "2") (pinfunction "2_2") (pintype "passive"))
      (node (ref "C12") (pin "2") (pinfunction "2_2") (pintype "passive"))
      (node (ref "CON1") (pin "1") (pintype "power_in"))
      (node (ref "D1") (pin "2") (pinfunction "K_2") (pintype "passive"))
      (node (ref "E1") (pin "1") (pinfunction "A_1") (pintype "passive"))
      (node (ref "IC2") (pin "24") (pinfunction "VCC_24") (pintype "power_in"))
      (node (ref "IC4") (pin "3") (pinfunction "VCC_3") (pintype "passive"))
      (node (ref "LED1") (pin "1") (pinfunction "A_1") (pintype "passive"))
      (node (ref "LED4") (pin "1") (pinfunction "A_1") (pintype "passive"))
      (node (ref "R14") (pin "1") (pinfunction "1_1") (pintype "passive"))
      (node (ref "U2") (pin "16") (pinfunction "VDD_16") (pintype "passive"))
      (node (ref "U3") (pin "16") (pinfunction "VDD_16") (pintype "passive"))
      (node (ref "U5") (pin "16") (pinfunction "VDD_16") (pintype "passive"))
      (node (ref "U6") (pin "16") (pinfunction "VDD_16") (pintype "passive"))
      (node (ref "U7") (pin "14") (pinfunction "VCC_14") (pintype "passive"))
      (node (ref "U8") (pin "14") (pinfunction "VCC_14") (pintype "passive"))
      (node (ref "U9") (pin "14") (pinfunction "VCC_14") (pintype "passive"))
      (node (ref "V1") (pin "3") (pinfunction "Vin_3") (pintype "passive"))
    )
    (net (code "78") (name "GND") (class "Default")
      (node (ref "C1") (pin "1") (pinfunction "1_1") (pintype "passive"))
      (node (ref "C10") (pin "1") (pinfunction "1_1") (pintype "passive"))
      (node (ref "C12") (pin "1") (pinfunction "1_1") (pintype "passive"))
      (node (ref "C13") (pin "1") (pinfunction "1_1") (pintype "passive"))
      (node (ref "C14") (pin "1") (pinfunction "1_1") (pintype "passive"))
      (node (ref "C15") (pin "2") (pinfunction "2_2") (pintype "passive"))
      (node (ref "C16") (pin "2") (pinfunction "2_2") (pintype "passive"))
      (node (ref "C17") (pin "2") (pinfunction "2_2") (pintype "passive"))
      (node (ref "C2") (pin "1") (pinfunction "1_1") (pintype "passive"))
      (node (ref "C3") (pin "2") (pinfunction "2_2") (pintype "passive"))
      (node (ref "C4") (pin "1") (pinfunction "1_1") (pintype "passive"))
      (node (ref "C6") (pin "1") (pinfunction "1_1") (pintype "passive"))
      (node (ref "C7") (pin "1") (pinfunction "1_1") (pintype "passive"))
      (node (ref "C8") (pin "1") (pinfunction "1_1") (pintype "passive"))
      (node (ref "C9") (pin "1") (pinfunction "1_1") (pintype "passive"))
      (node (ref "CON1") (pin "2") (pintype "power_in"))
      (node (ref "CON1") (pin "3") (pintype "power_in"))
      (node (ref "D1") (pin "1") (pinfunction "A_1") (pintype "passive"))
      (node (ref "D2") (pin "1") (pinfunction "A_1") (pintype "passive"))
      (node (ref "D3") (pin "1") (pinfunction "A_1") (pintype "passive"))
      (node (ref "D4") (pin "1") (pinfunction "A_1") (pintype "passive"))
      (node (ref "D5") (pin "1") (pinfunction "A_1") (pintype "passive"))
      (node (ref "E1") (pin "2") (pinfunction "K_2") (pintype "passive"))
      (node (ref "E2") (pin "2") (pinfunction "K_2") (pintype "passive"))
      (node (ref "E3") (pin "2") (pinfunction "K_2") (pintype "passive"))
      (node (ref "IC2") (pin "12") (pinfunction "GND_12") (pintype "power_in"))
      (node (ref "IC2") (pin "18") (pinfunction "~{G}1_18") (pintype "input"))
      (node (ref "IC2") (pin "19") (pinfunction "~{G}2_19") (pintype "input"))
      (node (ref "IC4") (pin "2") (pinfunction "GND_2") (pintype "passive"))
      (node (ref "IC4") (pin "8") (pinfunction "S_8") (pintype "passive"))
      (node (ref "JP1") (pin "1") (pinfunction "1_1") (pintype "passive"))
      (node (ref "LED5") (pin "2") (pinfunction "K_2") (pintype "passive"))
      (node (ref "R17") (pin "2") (pinfunction "2_2") (pintype "passive"))
      (node (ref "R18") (pin "1") (pinfunction "1_1") (pintype "passive"))
      (node (ref "R19") (pin "1") (pinfunction "1_1") (pintype "passive"))
      (node (ref "R19") (pin "2") (pinfunction "2_2") (pintype "passive"))
      (node (ref "R19") (pin "3") (pinfunction "3_3") (pintype "passive"))
      (node (ref "R19") (pin "4") (pinfunction "4_4") (pintype "passive"))
      (node (ref "R20") (pin "1") (pinfunction "1_1") (pintype "passive"))
      (node (ref "R20") (pin "2") (pinfunction "2_2") (pintype "passive"))
      (node (ref "R20") (pin "3") (pinfunction "3_3") (pintype "passive"))
      (node (ref "R20") (pin "4") (pinfunction "4_4") (pintype "passive"))
      (node (ref "R21") (pin "1") (pinfunction "1_1") (pintype "passive"))
      (node (ref "R22") (pin "2") (pinfunction "2_2") (pintype "passive"))
      (node (ref "R25") (pin "1") (pinfunction "1_1") (pintype "passive"))
      (node (ref "R25") (pin "2") (pinfunction "2_2") (pintype "passive"))
      (node (ref "R25") (pin "3") (pinfunction "3_3") (pintype "passive"))
      (node (ref "R25") (pin "4") (pinfunction "4_4") (pintype "passive"))
      (node (ref "R26") (pin "1") (pinfunction "1_1") (pintype "passive"))
      (node (ref "R26") (pin "2") (pinfunction "2_2") (pintype "passive"))
      (node (ref "R26") (pin "3") (pinfunction "3_3") (pintype "passive"))
      (node (ref "R26") (pin "4") (pinfunction "4_4") (pintype "passive"))
      (node (ref "R27") (pin "1") (pinfunction "1_1") (pintype "passive"))
      (node (ref "R27") (pin "2") (pinfunction "2_2") (pintype "passive"))
      (node (ref "R27") (pin "3") (pinfunction "3_3") (pintype "passive"))
      (node (ref "R27") (pin "4") (pinfunction "4_4") (pintype "passive"))
      (node (ref "R6") (pin "2") (pinfunction "2_2") (pintype "passive"))
      (node (ref "R8") (pin "2") (pinfunction "2_2") (pintype "passive"))
      (node (ref "SW1") (pin "2") (pinfunction "2_2") (pintype "passive"))
      (node (ref "U1") (pin "23") (pinfunction "VSS_1_23") (pintype "power_in"))
      (node (ref "U1") (pin "35") (pinfunction "VSS_2_35") (pintype "power_in"))
      (node (ref "U1") (pin "47") (pinfunction "VSS_3_47") (pintype "power_in"))
      (node (ref "U1") (pin "8") (pinfunction "VSSA_8") (pintype "power_in"))
      (node (ref "U2") (pin "6") (pinfunction "E#_6") (pintype "passive"))
      (node (ref "U2") (pin "7") (pinfunction "VEE_7") (pintype "passive"))
      (node (ref "U2") (pin "8") (pinfunction "VSS_8") (pintype "passive"))
      (node (ref "U3") (pin "6") (pinfunction "E#_6") (pintype "passive"))
      (node (ref "U3") (pin "7") (pinfunction "VEE_7") (pintype "passive"))
      (node (ref "U3") (pin "8") (pinfunction "VSS_8") (pintype "passive"))
      (node (ref "U4") (pin "11") (pinfunction "V-_11") (pintype "passive"))
      (node (ref "U5") (pin "6") (pinfunction "E#_6") (pintype "passive"))
      (node (ref "U5") (pin "7") (pinfunction "VEE_7") (pintype "passive"))
      (node (ref "U5") (pin "8") (pinfunction "VSS_8") (pintype "passive"))
      (node (ref "U6") (pin "6") (pinfunction "E#_6") (pintype "passive"))
      (node (ref "U6") (pin "7") (pinfunction "VEE_7") (pintype "passive"))
      (node (ref "U6") (pin "8") (pinfunction "VSS_8") (pintype "passive"))
      (node (ref "U7") (pin "7") (pinfunction "GND_7") (pintype "passive"))
      (node (ref "U8") (pin "7") (pinfunction "GND_7") (pintype "passive"))
      (node (ref "U9") (pin "7") (pinfunction "GND_7") (pintype "passive"))
      (node (ref "V1") (pin "1") (pinfunction "GND_1") (pintype "passive"))
    )
    (net (code "79") (name "Net-(IC4-CANH)") (class "Default")
      (node (ref "IC4") (pin "7") (pinfunction "CANH_7") (pintype "passive"))
      (node (ref "JP2") (pin "1") (pinfunction "1_1") (pintype "passive"))
      (node (ref "R10") (pin "1") (pinfunction "1_1") (pintype "passive"))
    )
    (net (code "80") (name "Net-(IC4-CANL)") (class "Default")
      (node (ref "IC4") (pin "6") (pinfunction "CANL_6") (pintype "passive"))
      (node (ref "JP2") (pin "2") (pinfunction "2_2") (pintype "passive"))
      (node (ref "R10") (pin "2") (pinfunction "2_2") (pintype "passive"))
    )
    (net (code "81") (name "Net-(LED1-K)") (class "Default")
      (node (ref "LED1") (pin "2") (pinfunction "K_2") (pintype "passive"))
      (node (ref "R9") (pin "2") (pinfunction "2_2") (pintype "passive"))
    )
    (net (code "82") (name "Net-(LED2-A)") (class "Default")
      (node (ref "LED2") (pin "1") (pinfunction "A_1") (pintype "passive"))
      (node (ref "R11") (pin "1") (pinfunction "1_1") (pintype "passive"))
    )
    (net (code "83") (name "Net-(LED4-K)") (class "Default")
      (node (ref "LED4") (pin "2") (pinfunction "K_2") (pintype "passive"))
      (node (ref "R13") (pin "2") (pinfunction "2_2") (pintype "passive"))
    )
    (net (code "84") (name "Net-(LED5-A)") (class "Default")
      (node (ref "LED5") (pin "1") (pinfunction "A_1") (pintype "passive"))
      (node (ref "R14") (pin "2") (pinfunction "2_2") (pintype "passive"))
    )
    (net (code "85") (name "Net-(U4--INA)") (class "Default")
      (node (ref "R15") (pin "1") (pinfunction "1_1") (pintype "passive"))
      (node (ref "R17") (pin "1") (pinfunction "1_1") (pintype "passive"))
      (node (ref "U4") (pin "2") (pinfunction "-INA_2") (pintype "passive"))
    )
    (net (code "86") (name "Net-(U4--INB)") (class "Default")
      (node (ref "R21") (pin "2") (pinfunction "2_2") (pintype "passive"))
      (node (ref "R24") (pin "1") (pinfunction "1_1") (pintype "passive"))
      (node (ref "U4") (pin "6") (pinfunction "-INB_6") (pintype "passive"))
    )
    (net (code "87") (name "Net-(U4--INC)") (class "Default")
      (node (ref "R22") (pin "1") (pinfunction "1_1") (pintype "passive"))
      (node (ref "R23") (pin "2") (pinfunction "2_2") (pintype "passive"))
      (node (ref "U4") (pin "9") (pinfunction "-INC_9") (pintype "passive"))
    )
    (net (code "88") (name "Net-(U4--IND)") (class "Default")
      (node (ref "R16") (pin "2") (pinfunction "2_2") (pintype "passive"))
      (node (ref "R18") (pin "2") (pinfunction "2_2") (pintype "passive"))
      (node (ref "U4") (pin "13") (pinfunction "-IND_13") (pintype "passive"))
    )
    (net (code "89") (name "unconnected-(IC2-Y15-Pad17)") (class "Default")
      (node (ref "IC2") (pin "17") (pinfunction "Y15_17") (pintype "output"))
    )
    (net (code "90") (name "unconnected-(IC4-VREF-Pad5)") (class "Default")
      (node (ref "IC4") (pin "5") (pinfunction "VREF_5") (pintype "passive+no_connect"))
    )
    (net (code "91") (name "unconnected-(R7-Pad5)") (class "Default")
      (node (ref "R7") (pin "5") (pinfunction "5_5") (pintype "passive"))
    )
    (net (code "92") (name "unconnected-(U1-I2C2_SCL{slash}PB10-Pad21)") (class "Default")
      (node (ref "U1") (pin "21") (pinfunction "I2C2_SCL/PB10_21") (pintype "bidirectional"))
    )
    (net (code "93") (name "unconnected-(U1-I2C2_SDA{slash}PB11-Pad22)") (class "Default")
      (node (ref "U1") (pin "22") (pinfunction "I2C2_SDA/PB11_22") (pintype "bidirectional"))
    )
    (net (code "94") (name "unconnected-(U1-PA4{slash}ADC12_IN4-Pad14)") (class "Default")
      (node (ref "U1") (pin "14") (pinfunction "PA4/ADC12_IN4_14") (pintype "bidirectional"))
    )
    (net (code "95") (name "unconnected-(U1-PA9{slash}USART1_TX-Pad30)") (class "Default")
      (node (ref "U1") (pin "30") (pinfunction "PA9/USART1_TX_30") (pintype "bidirectional"))
    )
    (net (code "96") (name "unconnected-(U1-PA10{slash}USART1_RX-Pad31)") (class "Default")
      (node (ref "U1") (pin "31") (pinfunction "PA10/USART1_RX_31") (pintype "bidirectional"))
    )
    (net (code "97") (name "unconnected-(U1-PA15{slash}JTDI-Pad38)") (class "Default")
      (node (ref "U1") (pin "38") (pinfunction "PA15/JTDI_38") (pintype "bidirectional"))
    )
    (net (code "98") (name "unconnected-(U1-PC13-TAMPER-RTC-Pad2)") (class "Default")
      (node (ref "U1") (pin "2") (pinfunction "PC13-TAMPER-RTC_2") (pintype "bidirectional"))
    )
    (net (code "99") (name "unconnected-(U1-PC14-OSC32_IN-Pad3)") (class "Default")
      (node (ref "U1") (pin "3") (pinfunction "PC14-OSC32_IN_3") (pintype "bidirectional"))
    )
    (net (code "100") (name "unconnected-(U1-PC15-OSC32_OUT-Pad4)") (class "Default")
      (node (ref "U1") (pin "4") (pinfunction "PC15-OSC32_OUT_4") (pintype "bidirectional"))
    )
    (net (code "101") (name "unconnected-(U1-SPI2_MISO{slash}PB14-Pad27)") (class "Default")
      (node (ref "U1") (pin "27") (pinfunction "SPI2_MISO/PB14_27") (pintype "bidirectional"))
    )
    (net (code "102") (name "unconnected-(U1-SPI2_MOSI{slash}PB15-Pad28)") (class "Default")
      (node (ref "U1") (pin "28") (pinfunction "SPI2_MOSI/PB15_28") (pintype "bidirectional"))
    )
    (net (code "103") (name "unconnected-(U1-SPI2_NSS{slash}PB12-Pad25)") (class "Default")
      (node (ref "U1") (pin "25") (pinfunction "SPI2_NSS/PB12_25") (pintype "bidirectional"))
    )
    (net (code "104") (name "unconnected-(U1-SPI2_SCK{slash}PB13-Pad26)") (class "Default")
      (node (ref "U1") (pin "26") (pinfunction "SPI2_SCK/PB13_26") (pintype "bidirectional"))
    )
    (net (code "105") (name "unconnected-(U1-TIM3_CH3{slash}PB0-Pad18)") (class "Default")
      (node (ref "U1") (pin "18") (pinfunction "TIM3_CH3/PB0_18") (pintype "bidirectional"))
    )
    (net (code "106") (name "unconnected-(U1-TIM3_CH4{slash}PB1-Pad19)") (class "Default")
      (node (ref "U1") (pin "19") (pinfunction "TIM3_CH4/PB1_19") (pintype "bidirectional"))
    )
    (net (code "107") (name "unconnected-(U1-TIM4_CH2{slash}PB7-Pad43)") (class "Default")
      (node (ref "U1") (pin "43") (pinfunction "TIM4_CH2/PB7_43") (pintype "bidirectional"))
    )
    (net (code "108") (name "unconnected-(U1-TIM4_CH3{slash}PB8-Pad45)") (class "Default")
      (node (ref "U1") (pin "45") (pinfunction "TIM4_CH3/PB8_45") (pintype "bidirectional"))
    )
    (net (code "109") (name "unconnected-(U1-TIM4_CH4{slash}PB9-Pad46)") (class "Default")
      (node (ref "U1") (pin "46") (pinfunction "TIM4_CH4/PB9_46") (pintype "bidirectional"))
    )
    (net (code "110") (name "unconnected-(U2-Y5-Pad5)") (class "Default")
      (node (ref "U2") (pin "5") (pinfunction "Y5_5") (pintype "passive"))
    )
    (net (code "111") (name "unconnected-(U2-Y6-Pad2)") (class "Default")
      (node (ref "U2") (pin "2") (pinfunction "Y6_2") (pintype "passive"))
    )
    (net (code "112") (name "unconnected-(U2-Y7-Pad4)") (class "Default")
      (node (ref "U2") (pin "4") (pinfunction "Y7_4") (pintype "passive"))
    )
    (net (code "113") (name "unconnected-(U3-Y5-Pad5)") (class "Default")
      (node (ref "U3") (pin "5") (pinfunction "Y5_5") (pintype "passive"))
    )
    (net (code "114") (name "unconnected-(U3-Y6-Pad2)") (class "Default")
      (node (ref "U3") (pin "2") (pinfunction "Y6_2") (pintype "passive"))
    )
    (net (code "115") (name "unconnected-(U3-Y7-Pad4)") (class "Default")
      (node (ref "U3") (pin "4") (pinfunction "Y7_4") (pintype "passive"))
    )
    (net (code "116") (name "unconnected-(U5-Y5-Pad5)") (class "Default")
      (node (ref "U5") (pin "5") (pinfunction "Y5_5") (pintype "passive"))
    )
    (net (code "117") (name "unconnected-(U5-Y6-Pad2)") (class "Default")
      (node (ref "U5") (pin "2") (pinfunction "Y6_2") (pintype "passive"))
    )
    (net (code "118") (name "unconnected-(U5-Y7-Pad4)") (class "Default")
      (node (ref "U5") (pin "4") (pinfunction "Y7_4") (pintype "passive"))
    )
    (net (code "119") (name "unconnected-(U6-Y5-Pad5)") (class "Default")
      (node (ref "U6") (pin "5") (pinfunction "Y5_5") (pintype "passive"))
    )
    (net (code "120") (name "unconnected-(U6-Y6-Pad2)") (class "Default")
      (node (ref "U6") (pin "2") (pinfunction "Y6_2") (pintype "passive"))
    )
    (net (code "121") (name "unconnected-(U6-Y7-Pad4)") (class "Default")
      (node (ref "U6") (pin "4") (pinfunction "Y7_4") (pintype "passive"))
    )
    (net (code "122") (name "unconnected-(U8-1A-Pad1)") (class "Default")
      (node (ref "U8") (pin "1") (pinfunction "1A_1") (pintype "passive"))
    )
    (net (code "123") (name "unconnected-(U8-1Y-Pad2)") (class "Default")
      (node (ref "U8") (pin "2") (pinfunction "1Y_2") (pintype "passive"))
    )
    (net (code "124") (name "unconnected-(U8-2A-Pad3)") (class "Default")
      (node (ref "U8") (pin "3") (pinfunction "2A_3") (pintype "passive"))
    )
    (net (code "125") (name "unconnected-(U8-2Y-Pad4)") (class "Default")
      (node (ref "U8") (pin "4") (pinfunction "2Y_4") (pintype "passive"))
    )
    (net (code "126") (name "unconnected-(U8-3A-Pad5)") (class "Default")
      (node (ref "U8") (pin "5") (pinfunction "3A_5") (pintype "passive"))
    )
    (net (code "127") (name "unconnected-(U8-3Y-Pad6)") (class "Default")
      (node (ref "U8") (pin "6") (pinfunction "3Y_6") (pintype "passive"))
    )
  )
)
